# temp-sensor.net
KiCad netlist of a schematic drawn in EAGLE
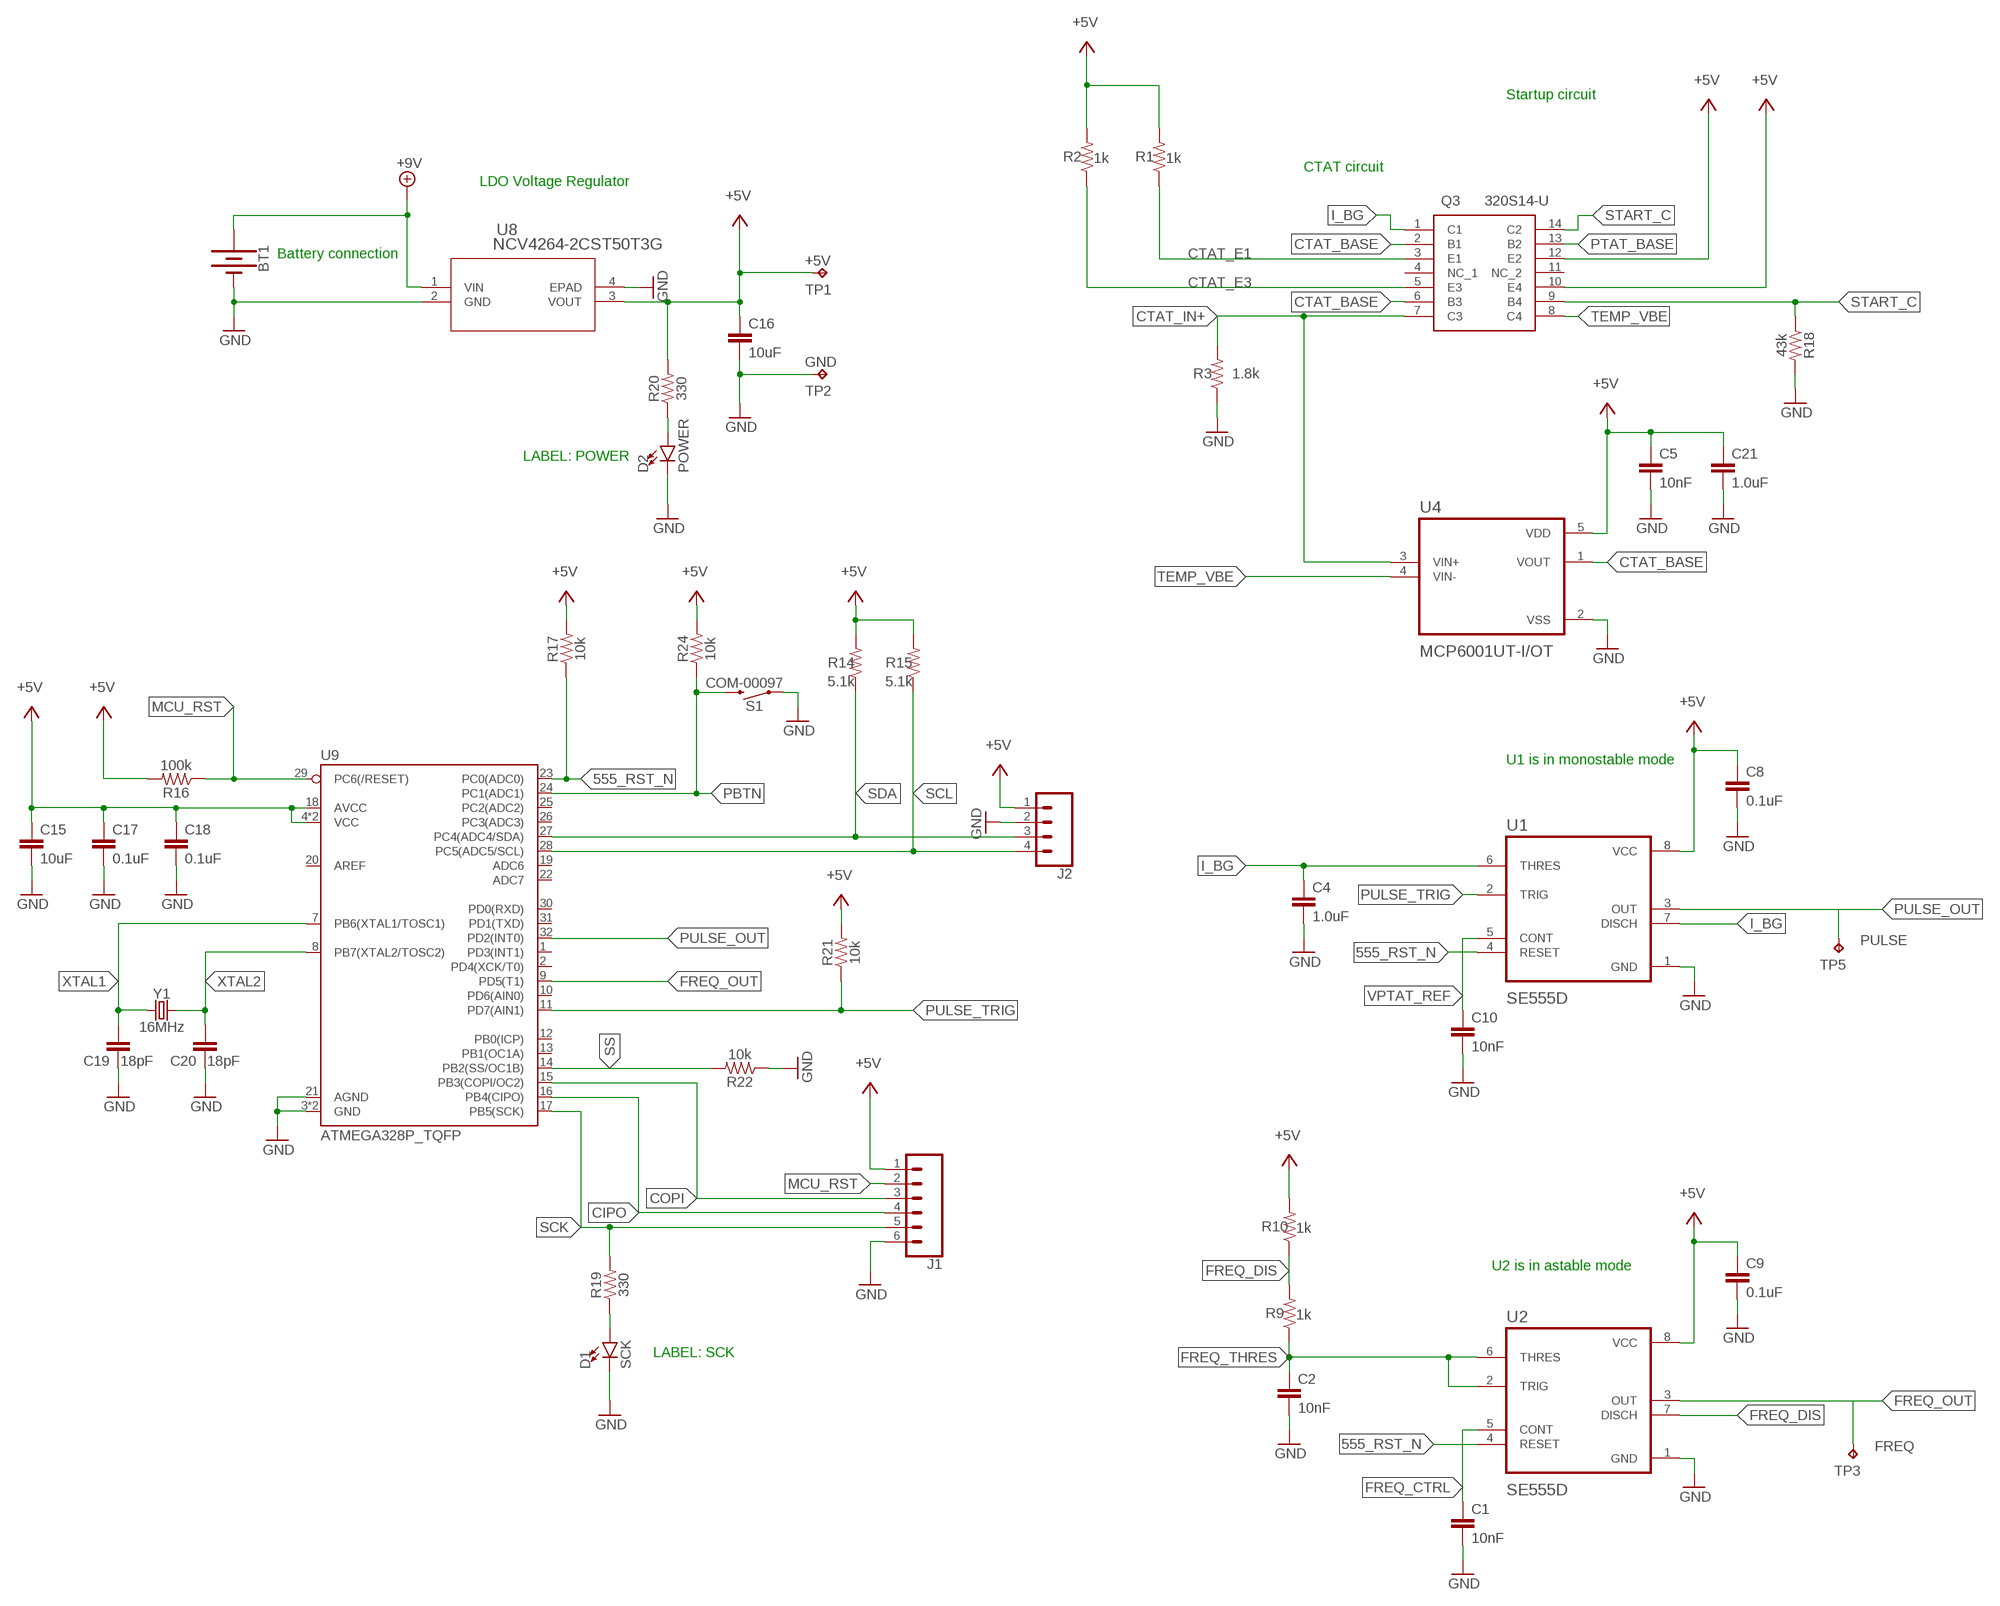
[diagram p0: schematic, sheet 1, part 1 of 2]
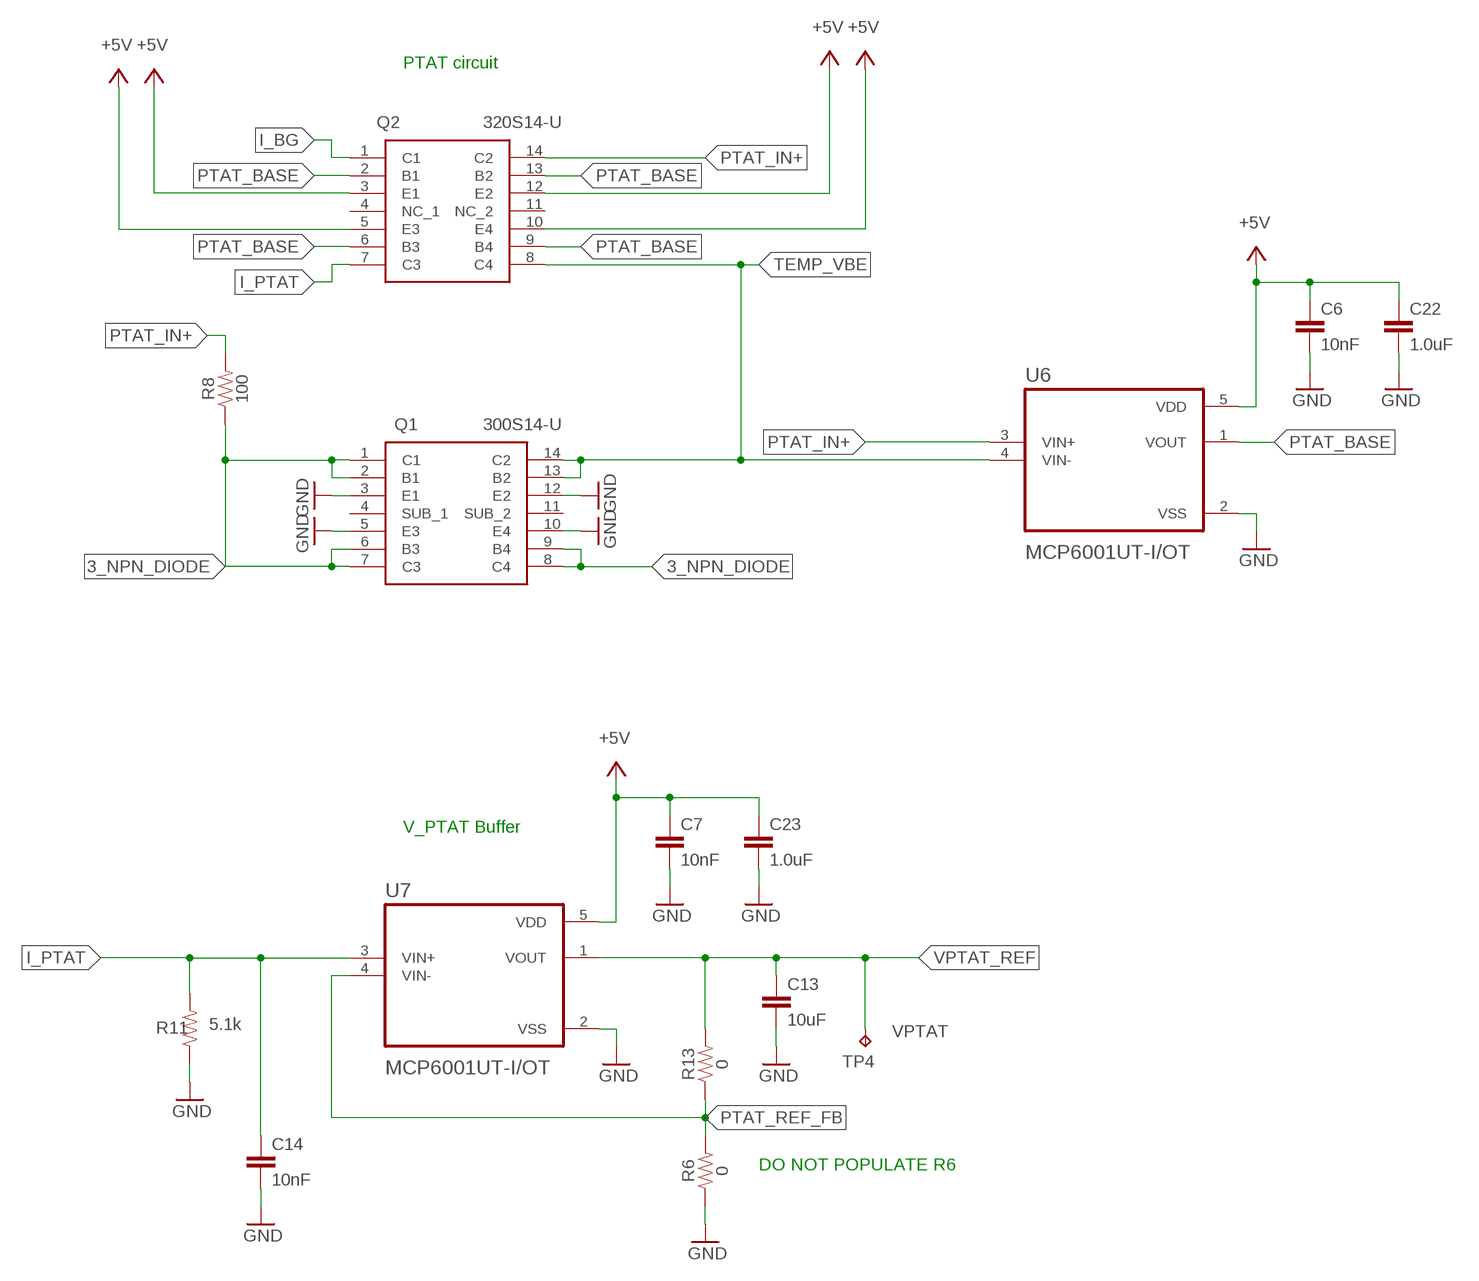
[diagram p1: schematic, sheet 1, part 2 of 2]

(export (version "E")
  (design (tool "Eeschema 10.0.6"))
  (components
    (comp (ref "BT1")
      (value "BATTERY-9V")
      (footprint "eagle-import:BATTCON_9V")
      (libsource (lib "eagle-import") (part "BATTERY-9V"))
    )
    (comp (ref "C1")
      (value "10nF")
      (footprint "eagle-import:0603")
      (libsource (lib "eagle-import") (part "10NF-0603-50V-10%"))
    )
    (comp (ref "C2")
      (value "10nF")
      (footprint "eagle-import:0603")
      (libsource (lib "eagle-import") (part "10NF-0603-50V-10%"))
    )
    (comp (ref "C4")
      (value "1.0uF")
      (footprint "eagle-import:0603")
      (libsource (lib "eagle-import") (part "1.0UF-0603-16V-10%-X7R"))
    )
    (comp (ref "C5")
      (value "10nF")
      (footprint "eagle-import:0603")
      (libsource (lib "eagle-import") (part "10NF-0603-50V-10%"))
    )
    (comp (ref "C6")
      (value "10nF")
      (footprint "eagle-import:0603")
      (libsource (lib "eagle-import") (part "10NF-0603-50V-10%"))
    )
    (comp (ref "C7")
      (value "10nF")
      (footprint "eagle-import:0603")
      (libsource (lib "eagle-import") (part "10NF-0603-50V-10%"))
    )
    (comp (ref "C8")
      (value "0.1uF")
      (footprint "eagle-import:0603")
      (libsource (lib "eagle-import") (part "0.1UF-0603-25V-10%-X7R-WE"))
    )
    (comp (ref "C9")
      (value "0.1uF")
      (footprint "eagle-import:0603")
      (libsource (lib "eagle-import") (part "0.1UF-0603-25V-10%-X7R-WE"))
    )
    (comp (ref "C10")
      (value "10nF")
      (footprint "eagle-import:0603")
      (libsource (lib "eagle-import") (part "10NF-0603-50V-10%"))
    )
    (comp (ref "C13")
      (value "10uF")
      (footprint "eagle-import:0805")
      (libsource (lib "eagle-import") (part "10UF-0805-25V-10%"))
    )
    (comp (ref "C14")
      (value "10nF")
      (footprint "eagle-import:0603")
      (libsource (lib "eagle-import") (part "10NF-0603-50V-10%"))
    )
    (comp (ref "C15")
      (value "10uF")
      (footprint "eagle-import:0805")
      (libsource (lib "eagle-import") (part "10UF-0805-25V-10%"))
    )
    (comp (ref "C16")
      (value "10uF")
      (footprint "eagle-import:0805")
      (libsource (lib "eagle-import") (part "10UF-0805-25V-10%"))
    )
    (comp (ref "C17")
      (value "0.1uF")
      (footprint "eagle-import:0603")
      (libsource (lib "eagle-import") (part "0.1UF-0603-25V-10%-X7R-WE"))
    )
    (comp (ref "C18")
      (value "0.1uF")
      (footprint "eagle-import:0603")
      (libsource (lib "eagle-import") (part "0.1UF-0603-25V-10%-X7R-WE"))
    )
    (comp (ref "C19")
      (value "18pF")
      (footprint "eagle-import:0603")
      (libsource (lib "eagle-import") (part "18PF-0603-50V-5%"))
    )
    (comp (ref "C20")
      (value "18pF")
      (footprint "eagle-import:0603")
      (libsource (lib "eagle-import") (part "18PF-0603-50V-5%"))
    )
    (comp (ref "C21")
      (value "1.0uF")
      (footprint "eagle-import:0603")
      (libsource (lib "eagle-import") (part "1.0UF-0603-16V-10%-X7R"))
    )
    (comp (ref "C22")
      (value "1.0uF")
      (footprint "eagle-import:0603")
      (libsource (lib "eagle-import") (part "1.0UF-0603-16V-10%-X7R"))
    )
    (comp (ref "C23")
      (value "1.0uF")
      (footprint "eagle-import:0603")
      (libsource (lib "eagle-import") (part "1.0UF-0603-16V-10%-X7R"))
    )
    (comp (ref "D1")
      (value "SCK")
      (footprint "eagle-import:LED-1206")
      (libsource (lib "eagle-import") (part "LED-GREEN1206"))
    )
    (comp (ref "D2")
      (value "POWER")
      (footprint "eagle-import:LED-1206")
      (libsource (lib "eagle-import") (part "LED-GREEN1206"))
    )
    (comp (ref "J1")
      (value "CONN_06SILK_FEMALE_PTH")
      (footprint "eagle-import:1X06")
      (libsource (lib "eagle-import") (part "CONN_06SILK_FEMALE_PTH"))
    )
    (comp (ref "J2")
      (value "CONN_04PTH")
      (footprint "eagle-import:1X04")
      (libsource (lib "eagle-import") (part "CONN_04PTH"))
    )
    (comp (ref "Q1")
      (value "300S14-U")
      (footprint "eagle-import:SOIC127P602X175-14N")
      (fields (field (name "MOUSER_PART_NUMBER") "887-300S14-U"))
      (libsource (lib "eagle-import") (part "300S14-U"))
    )
    (comp (ref "Q2")
      (value "320S14-U")
      (footprint "eagle-import:SOIC127P602X175-14N")
      (fields (field (name "MOUSER_PART_NUMBER") "887-320S14-U"))
      (libsource (lib "eagle-import") (part "320S14-U"))
    )
    (comp (ref "Q3")
      (value "320S14-U")
      (footprint "eagle-import:SOIC127P602X175-14N")
      (fields (field (name "MOUSER_PART_NUMBER") "887-320S14-U"))
      (libsource (lib "eagle-import") (part "320S14-U"))
    )
    (comp (ref "R1")
      (value "1k")
      (footprint "eagle-import:0603")
      (libsource (lib "eagle-import") (part "1KOHM-0603-1/10W-1%"))
    )
    (comp (ref "R2")
      (value "1k")
      (footprint "eagle-import:0603")
      (libsource (lib "eagle-import") (part "1KOHM-0603-1/10W-1%"))
    )
    (comp (ref "R3")
      (value "1.8k")
      (footprint "eagle-import:0603")
      (libsource (lib "eagle-import") (part "1.8KOHM-0603-1/10W-1%"))
    )
    (comp (ref "R6")
      (value "0")
      (footprint "eagle-import:0603")
      (libsource (lib "eagle-import") (part "0OHM-0603-1/10W"))
    )
    (comp (ref "R8")
      (value "100")
      (footprint "eagle-import:0603")
      (libsource (lib "eagle-import") (part "100OHM-0603-1/10W-1%"))
    )
    (comp (ref "R9")
      (value "1k")
      (footprint "eagle-import:0603")
      (libsource (lib "eagle-import") (part "1KOHM-0603-1/10W-1%"))
    )
    (comp (ref "R10")
      (value "1k")
      (footprint "eagle-import:0603")
      (libsource (lib "eagle-import") (part "1KOHM-0603-1/10W-1%"))
    )
    (comp (ref "R11")
      (value "5.1k")
      (footprint "eagle-import:0603")
      (libsource (lib "eagle-import") (part "5.1KOHM5.1KOHM-0603-1/10W-1%"))
    )
    (comp (ref "R13")
      (value "0")
      (footprint "eagle-import:0603")
      (libsource (lib "eagle-import") (part "0OHM-0603-1/10W"))
    )
    (comp (ref "R14")
      (value "5.1k")
      (footprint "eagle-import:0603")
      (libsource (lib "eagle-import") (part "5.1KOHM5.1KOHM-0603-1/10W-1%"))
    )
    (comp (ref "R15")
      (value "5.1k")
      (footprint "eagle-import:0603")
      (libsource (lib "eagle-import") (part "5.1KOHM5.1KOHM-0603-1/10W-1%"))
    )
    (comp (ref "R16")
      (value "100k")
      (footprint "eagle-import:0603")
      (libsource (lib "eagle-import") (part "100KOHM-0603-1/10W-1%"))
    )
    (comp (ref "R17")
      (value "10k")
      (footprint "eagle-import:0603")
      (libsource (lib "eagle-import") (part "10KOHM-0603-1/10W-1%"))
    )
    (comp (ref "R18")
      (value "43k")
      (footprint "eagle-import:0603")
      (libsource (lib "eagle-import") (part "43KOHM-0603-1/10W-1%"))
    )
    (comp (ref "R19")
      (value "330")
      (footprint "eagle-import:0603")
      (libsource (lib "eagle-import") (part "330OHM-0603-1/10W-1%"))
    )
    (comp (ref "R20")
      (value "330")
      (footprint "eagle-import:0603")
      (libsource (lib "eagle-import") (part "330OHM-0603-1/10W-1%"))
    )
    (comp (ref "R21")
      (value "10k")
      (footprint "eagle-import:0603")
      (libsource (lib "eagle-import") (part "10KOHM-0603-1/10W-1%"))
    )
    (comp (ref "R22")
      (value "10k")
      (footprint "eagle-import:0603")
      (libsource (lib "eagle-import") (part "10KOHM-0603-1/10W-1%"))
    )
    (comp (ref "R24")
      (value "10k")
      (footprint "eagle-import:0603")
      (libsource (lib "eagle-import") (part "10KOHM-0603-1/10W-1%"))
    )
    (comp (ref "S1")
      (value "MOMENTARY-SWITCH-SPST-PTH-6.0MM")
      (footprint "eagle-import:TACTILE_SWITCH_PTH_6.0MM")
      (fields (field (name "SF_SKU") "COM-00097"))
      (libsource (lib "eagle-import") (part "MOMENTARY-SWITCH-SPST-PTH-6.0MM"))
    )
    (comp (ref "TP1")
      (value "TPPAD1-13")
      (footprint "eagle-import:P1-13")
      (fields (field (name "TP_SIGNAL_NAME") "+5V"))
      (libsource (lib "eagle-import") (part "TPPAD1-13"))
    )
    (comp (ref "TP2")
      (value "TPPAD1-13")
      (footprint "eagle-import:P1-13")
      (fields (field (name "TP_SIGNAL_NAME") "GND"))
      (libsource (lib "eagle-import") (part "TPPAD1-13"))
    )
    (comp (ref "TP3")
      (value "TPPAD1-13")
      (footprint "eagle-import:P1-13")
      (fields (field (name "TP_SIGNAL_NAME") "FREQ"))
      (libsource (lib "eagle-import") (part "TPPAD1-13"))
    )
    (comp (ref "TP4")
      (value "TPPAD1-13")
      (footprint "eagle-import:P1-13")
      (fields (field (name "TP_SIGNAL_NAME") "VPTAT"))
      (libsource (lib "eagle-import") (part "TPPAD1-13"))
    )
    (comp (ref "TP5")
      (value "TPPAD1-13")
      (footprint "eagle-import:P1-13")
      (fields (field (name "TP_SIGNAL_NAME") "PULSE"))
      (libsource (lib "eagle-import") (part "TPPAD1-13"))
    )
    (comp (ref "U1")
      (value "SE555D")
      (footprint "eagle-import:SOIC127P599X175-8N")
      (fields (field (name "MF") "Texas Instruments"))
      (libsource (lib "eagle-import") (part "SE555D"))
    )
    (comp (ref "U2")
      (value "SE555D")
      (footprint "eagle-import:SOIC127P599X175-8N")
      (fields (field (name "MF") "Texas Instruments"))
      (libsource (lib "eagle-import") (part "SE555D"))
    )
    (comp (ref "U4")
      (value "MCP6001UT-I/OT")
      (footprint "eagle-import:SOT95P270X145-5N")
      (libsource (lib "eagle-import") (part "MCP6001UT-I/OT"))
    )
    (comp (ref "U6")
      (value "MCP6001UT-I/OT")
      (footprint "eagle-import:SOT95P270X145-5N")
      (libsource (lib "eagle-import") (part "MCP6001UT-I/OT"))
    )
    (comp (ref "U7")
      (value "MCP6001UT-I/OT")
      (footprint "eagle-import:SOT95P270X145-5N")
      (libsource (lib "eagle-import") (part "MCP6001UT-I/OT"))
    )
    (comp (ref "U8")
      (value "NCV4264-2CST50T3G")
      (footprint "eagle-import:SOT-223_ONS")
      (fields (field (name "COPYRIGHT") "Copyright (C) 2024 Ultra Librarian. All rights reserved."))
      (libsource (lib "eagle-import") (part "NCV4264-2CST50T3G"))
    )
    (comp (ref "U9")
      (value "ATMEGA328P_TQFP")
      (footprint "eagle-import:TQFP32-08")
      (libsource (lib "eagle-import") (part "ATMEGA328P_TQFP"))
    )
    (comp (ref "Y1")
      (value "16MHz")
      (footprint "eagle-import:CRYSTAL-SMD-5X3.2-4PAD")
      (libsource (lib "eagle-import") (part "CRYSTAL-16MHZSMD-5X3.2"))
    )
  )
  (nets
    (net (code "1") (name "+5V") (class "Default")
      (node (ref "C15") (pin "1") (pinfunction "1_1") (pintype "passive"))
      (node (ref "C16") (pin "1") (pinfunction "1_1") (pintype "passive"))
      (node (ref "C17") (pin "1") (pinfunction "1_1") (pintype "passive"))
      (node (ref "C18") (pin "1") (pinfunction "1_1") (pintype "passive"))
      (node (ref "C21") (pin "1") (pinfunction "1_1") (pintype "passive"))
      (node (ref "C22") (pin "1") (pinfunction "1_1") (pintype "passive"))
      (node (ref "C23") (pin "1") (pinfunction "1_1") (pintype "passive"))
      (node (ref "C5") (pin "1") (pinfunction "1_1") (pintype "passive"))
      (node (ref "C6") (pin "1") (pinfunction "1_1") (pintype "passive"))
      (node (ref "C7") (pin "1") (pinfunction "1_1") (pintype "passive"))
      (node (ref "C8") (pin "1") (pinfunction "1_1") (pintype "passive"))
      (node (ref "C9") (pin "1") (pinfunction "1_1") (pintype "passive"))
      (node (ref "J1") (pin "1") (pinfunction "1_1") (pintype "passive"))
      (node (ref "J2") (pin "1") (pinfunction "1_1") (pintype "passive"))
      (node (ref "Q2") (pin "10") (pinfunction "E4_10") (pintype "bidirectional"))
      (node (ref "Q2") (pin "12") (pinfunction "E2_12") (pintype "bidirectional"))
      (node (ref "Q2") (pin "3") (pinfunction "E1_3") (pintype "bidirectional"))
      (node (ref "Q2") (pin "5") (pinfunction "E3_5") (pintype "bidirectional"))
      (node (ref "Q3") (pin "10") (pinfunction "E4_10") (pintype "bidirectional"))
      (node (ref "Q3") (pin "12") (pinfunction "E2_12") (pintype "bidirectional"))
      (node (ref "R1") (pin "2") (pinfunction "2_2") (pintype "passive"))
      (node (ref "R10") (pin "2") (pinfunction "2_2") (pintype "passive"))
      (node (ref "R14") (pin "2") (pinfunction "2_2") (pintype "passive"))
      (node (ref "R15") (pin "2") (pinfunction "2_2") (pintype "passive"))
      (node (ref "R16") (pin "2") (pinfunction "2_2") (pintype "passive"))
      (node (ref "R17") (pin "2") (pinfunction "2_2") (pintype "passive"))
      (node (ref "R2") (pin "2") (pinfunction "2_2") (pintype "passive"))
      (node (ref "R20") (pin "2") (pinfunction "2_2") (pintype "passive"))
      (node (ref "R21") (pin "2") (pinfunction "2_2") (pintype "passive"))
      (node (ref "R24") (pin "2") (pinfunction "2_2") (pintype "passive"))
      (node (ref "TP1") (pin "TP") (pinfunction "TP_TP") (pintype "input"))
      (node (ref "U1") (pin "8") (pinfunction "VCC_8") (pintype "power_in"))
      (node (ref "U2") (pin "8") (pinfunction "VCC_8") (pintype "power_in"))
      (node (ref "U4") (pin "5") (pinfunction "VDD_5") (pintype "power_in"))
      (node (ref "U6") (pin "5") (pinfunction "VDD_5") (pintype "power_in"))
      (node (ref "U7") (pin "5") (pinfunction "VDD_5") (pintype "power_in"))
      (node (ref "U8") (pin "3") (pinfunction "VOUT_3") (pintype "output"))
      (node (ref "U9") (pin "18") (pinfunction "AVCC_18") (pintype "bidirectional"))
      (node (ref "U9") (pin "4") (pinfunction "VCC_4") (pintype "bidirectional"))
      (node (ref "U9") (pin "6") (pinfunction "VCC_6") (pintype "bidirectional"))
    )
    (net (code "2") (name "+9V") (class "Default")
      (node (ref "BT1") (pin "+") (pinfunction "+_+") (pintype "power_in"))
      (node (ref "U8") (pin "1") (pinfunction "VIN_1") (pintype "passive"))
    )
    (net (code "3") (name "/CTAT_E1") (class "Default")
      (node (ref "Q3") (pin "3") (pinfunction "E1_3") (pintype "bidirectional"))
      (node (ref "R1") (pin "1") (pinfunction "1_1") (pintype "passive"))
    )
    (net (code "4") (name "/CTAT_E3") (class "Default")
      (node (ref "Q3") (pin "5") (pinfunction "E3_5") (pintype "bidirectional"))
      (node (ref "R2") (pin "1") (pinfunction "1_1") (pintype "passive"))
    )
    (net (code "5") (name "3_NPN_DIODE") (class "Default")
      (node (ref "Q1") (pin "1") (pinfunction "C1_1") (pintype "bidirectional"))
      (node (ref "Q1") (pin "2") (pinfunction "B1_2") (pintype "bidirectional"))
      (node (ref "Q1") (pin "6") (pinfunction "B3_6") (pintype "bidirectional"))
      (node (ref "Q1") (pin "7") (pinfunction "C3_7") (pintype "bidirectional"))
      (node (ref "Q1") (pin "8") (pinfunction "C4_8") (pintype "bidirectional"))
      (node (ref "Q1") (pin "9") (pinfunction "B4_9") (pintype "bidirectional"))
      (node (ref "R8") (pin "1") (pinfunction "1_1") (pintype "passive"))
    )
    (net (code "6") (name "555_RST_N") (class "Default")
      (node (ref "R17") (pin "1") (pinfunction "1_1") (pintype "passive"))
      (node (ref "U1") (pin "4") (pinfunction "RESET_4") (pintype "input"))
      (node (ref "U2") (pin "4") (pinfunction "RESET_4") (pintype "input"))
      (node (ref "U9") (pin "23") (pinfunction "PC0(ADC0)_23") (pintype "bidirectional"))
    )
    (net (code "7") (name "CIPO") (class "Default")
      (node (ref "J1") (pin "4") (pinfunction "4_4") (pintype "passive"))
      (node (ref "U9") (pin "16") (pinfunction "PB4(CIPO)_16") (pintype "bidirectional"))
    )
    (net (code "8") (name "COPI") (class "Default")
      (node (ref "J1") (pin "3") (pinfunction "3_3") (pintype "passive"))
      (node (ref "U9") (pin "15") (pinfunction "PB3(COPI/OC2)_15") (pintype "bidirectional"))
    )
    (net (code "9") (name "CTAT_BASE") (class "Default")
      (node (ref "Q3") (pin "2") (pinfunction "B1_2") (pintype "bidirectional"))
      (node (ref "Q3") (pin "6") (pinfunction "B3_6") (pintype "bidirectional"))
      (node (ref "U4") (pin "1") (pinfunction "VOUT_1") (pintype "output"))
    )
    (net (code "10") (name "CTAT_IN+") (class "Default")
      (node (ref "Q3") (pin "7") (pinfunction "C3_7") (pintype "bidirectional"))
      (node (ref "R3") (pin "2") (pinfunction "2_2") (pintype "passive"))
      (node (ref "U4") (pin "3") (pinfunction "VIN+_3") (pintype "input"))
    )
    (net (code "11") (name "FREQ_CTRL") (class "Default")
      (node (ref "C1") (pin "1") (pinfunction "1_1") (pintype "passive"))
      (node (ref "U2") (pin "5") (pinfunction "CONT_5") (pintype "bidirectional"))
    )
    (net (code "12") (name "FREQ_DIS") (class "Default")
      (node (ref "R10") (pin "1") (pinfunction "1_1") (pintype "passive"))
      (node (ref "R9") (pin "2") (pinfunction "2_2") (pintype "passive"))
      (node (ref "U2") (pin "7") (pinfunction "DISCH_7") (pintype "output"))
    )
    (net (code "13") (name "FREQ_OUT") (class "Default")
      (node (ref "TP3") (pin "TP") (pinfunction "TP_TP") (pintype "input"))
      (node (ref "U2") (pin "3") (pinfunction "OUT_3") (pintype "output"))
      (node (ref "U9") (pin "9") (pinfunction "PD5(T1)_9") (pintype "bidirectional"))
    )
    (net (code "14") (name "FREQ_THRES") (class "Default")
      (node (ref "C2") (pin "1") (pinfunction "1_1") (pintype "passive"))
      (node (ref "R9") (pin "1") (pinfunction "1_1") (pintype "passive"))
      (node (ref "U2") (pin "2") (pinfunction "TRIG_2") (pintype "input"))
      (node (ref "U2") (pin "6") (pinfunction "THRES_6") (pintype "input"))
    )
    (net (code "15") (name "GND") (class "Default")
      (node (ref "BT1") (pin "-") (pinfunction "-_-") (pintype "power_in"))
      (node (ref "C1") (pin "2") (pinfunction "2_2") (pintype "passive"))
      (node (ref "C10") (pin "2") (pinfunction "2_2") (pintype "passive"))
      (node (ref "C13") (pin "2") (pinfunction "2_2") (pintype "passive"))
      (node (ref "C14") (pin "2") (pinfunction "2_2") (pintype "passive"))
      (node (ref "C15") (pin "2") (pinfunction "2_2") (pintype "passive"))
      (node (ref "C16") (pin "2") (pinfunction "2_2") (pintype "passive"))
      (node (ref "C17") (pin "2") (pinfunction "2_2") (pintype "passive"))
      (node (ref "C18") (pin "2") (pinfunction "2_2") (pintype "passive"))
      (node (ref "C19") (pin "1") (pinfunction "1_1") (pintype "passive"))
      (node (ref "C2") (pin "2") (pinfunction "2_2") (pintype "passive"))
      (node (ref "C20") (pin "1") (pinfunction "1_1") (pintype "passive"))
      (node (ref "C21") (pin "2") (pinfunction "2_2") (pintype "passive"))
      (node (ref "C22") (pin "2") (pinfunction "2_2") (pintype "passive"))
      (node (ref "C23") (pin "2") (pinfunction "2_2") (pintype "passive"))
      (node (ref "C4") (pin "2") (pinfunction "2_2") (pintype "passive"))
      (node (ref "C5") (pin "2") (pinfunction "2_2") (pintype "passive"))
      (node (ref "C6") (pin "2") (pinfunction "2_2") (pintype "passive"))
      (node (ref "C7") (pin "2") (pinfunction "2_2") (pintype "passive"))
      (node (ref "C8") (pin "2") (pinfunction "2_2") (pintype "passive"))
      (node (ref "C9") (pin "2") (pinfunction "2_2") (pintype "passive"))
      (node (ref "D1") (pin "C") (pinfunction "C_C") (pintype "passive"))
      (node (ref "D2") (pin "C") (pinfunction "C_C") (pintype "passive"))
      (node (ref "J1") (pin "6") (pinfunction "6_6") (pintype "passive"))
      (node (ref "J2") (pin "2") (pinfunction "2_2") (pintype "passive"))
      (node (ref "Q1") (pin "10") (pinfunction "E4_10") (pintype "bidirectional"))
      (node (ref "Q1") (pin "12") (pinfunction "E2_12") (pintype "bidirectional"))
      (node (ref "Q1") (pin "3") (pinfunction "E1_3") (pintype "bidirectional"))
      (node (ref "Q1") (pin "5") (pinfunction "E3_5") (pintype "bidirectional"))
      (node (ref "R11") (pin "1") (pinfunction "1_1") (pintype "passive"))
      (node (ref "R18") (pin "2") (pinfunction "2_2") (pintype "passive"))
      (node (ref "R22") (pin "1") (pinfunction "1_1") (pintype "passive"))
      (node (ref "R3") (pin "1") (pinfunction "1_1") (pintype "passive"))
      (node (ref "R6") (pin "1") (pinfunction "1_1") (pintype "passive"))
      (node (ref "S1") (pin "1") (pinfunction "1_1") (pintype "passive"))
      (node (ref "TP2") (pin "TP") (pinfunction "TP_TP") (pintype "input"))
      (node (ref "U1") (pin "1") (pinfunction "GND_1") (pintype "power_in"))
      (node (ref "U2") (pin "1") (pinfunction "GND_1") (pintype "power_in"))
      (node (ref "U4") (pin "2") (pinfunction "VSS_2") (pintype "power_in"))
      (node (ref "U6") (pin "2") (pinfunction "VSS_2") (pintype "power_in"))
      (node (ref "U7") (pin "2") (pinfunction "VSS_2") (pintype "power_in"))
      (node (ref "U8") (pin "2") (pinfunction "GND_2") (pintype "passive"))
      (node (ref "U8") (pin "4") (pinfunction "EPAD_4") (pintype "passive"))
      (node (ref "U9") (pin "21") (pinfunction "AGND_21") (pintype "bidirectional"))
      (node (ref "U9") (pin "3") (pinfunction "GND_3") (pintype "bidirectional"))
      (node (ref "U9") (pin "5") (pinfunction "GND_5") (pintype "bidirectional"))
    )
    (net (code "16") (name "I_BG") (class "Default")
      (node (ref "C4") (pin "1") (pinfunction "1_1") (pintype "passive"))
      (node (ref "Q2") (pin "1") (pinfunction "C1_1") (pintype "bidirectional"))
      (node (ref "Q3") (pin "1") (pinfunction "C1_1") (pintype "bidirectional"))
      (node (ref "U1") (pin "6") (pinfunction "THRES_6") (pintype "input"))
      (node (ref "U1") (pin "7") (pinfunction "DISCH_7") (pintype "output"))
    )
    (net (code "17") (name "I_PTAT") (class "Default")
      (node (ref "C14") (pin "1") (pinfunction "1_1") (pintype "passive"))
      (node (ref "Q2") (pin "7") (pinfunction "C3_7") (pintype "bidirectional"))
      (node (ref "R11") (pin "2") (pinfunction "2_2") (pintype "passive"))
      (node (ref "U7") (pin "3") (pinfunction "VIN+_3") (pintype "input"))
    )
    (net (code "18") (name "MCU_RST") (class "Default")
      (node (ref "J1") (pin "2") (pinfunction "2_2") (pintype "passive"))
      (node (ref "R16") (pin "1") (pinfunction "1_1") (pintype "passive"))
      (node (ref "U9") (pin "29") (pinfunction "PC6(/RESET)_29") (pintype "bidirectional"))
    )
    (net (code "19") (name "Net-(D1-PadA)") (class "Default")
      (node (ref "D1") (pin "A") (pinfunction "A_A") (pintype "passive"))
      (node (ref "R19") (pin "1") (pinfunction "1_1") (pintype "passive"))
    )
    (net (code "20") (name "Net-(D2-PadA)") (class "Default")
      (node (ref "D2") (pin "A") (pinfunction "A_A") (pintype "passive"))
      (node (ref "R20") (pin "1") (pinfunction "1_1") (pintype "passive"))
    )
    (net (code "21") (name "PBTN") (class "Default")
      (node (ref "R24") (pin "1") (pinfunction "1_1") (pintype "passive"))
      (node (ref "S1") (pin "3") (pinfunction "2_3") (pintype "passive"))
      (node (ref "U9") (pin "24") (pinfunction "PC1(ADC1)_24") (pintype "bidirectional"))
    )
    (net (code "22") (name "PTAT_BASE") (class "Default")
      (node (ref "Q2") (pin "13") (pinfunction "B2_13") (pintype "bidirectional"))
      (node (ref "Q2") (pin "2") (pinfunction "B1_2") (pintype "bidirectional"))
      (node (ref "Q2") (pin "6") (pinfunction "B3_6") (pintype "bidirectional"))
      (node (ref "Q2") (pin "9") (pinfunction "B4_9") (pintype "bidirectional"))
      (node (ref "Q3") (pin "13") (pinfunction "B2_13") (pintype "bidirectional"))
      (node (ref "U6") (pin "1") (pinfunction "VOUT_1") (pintype "output"))
    )
    (net (code "23") (name "PTAT_IN+") (class "Default")
      (node (ref "Q2") (pin "14") (pinfunction "C2_14") (pintype "bidirectional"))
      (node (ref "R8") (pin "2") (pinfunction "2_2") (pintype "passive"))
      (node (ref "U6") (pin "3") (pinfunction "VIN+_3") (pintype "input"))
    )
    (net (code "24") (name "PTAT_REF_FB") (class "Default")
      (node (ref "R13") (pin "1") (pinfunction "1_1") (pintype "passive"))
      (node (ref "R6") (pin "2") (pinfunction "2_2") (pintype "passive"))
      (node (ref "U7") (pin "4") (pinfunction "VIN-_4") (pintype "input"))
    )
    (net (code "25") (name "PULSE_OUT") (class "Default")
      (node (ref "TP5") (pin "TP") (pinfunction "TP_TP") (pintype "input"))
      (node (ref "U1") (pin "3") (pinfunction "OUT_3") (pintype "output"))
      (node (ref "U9") (pin "32") (pinfunction "PD2(INT0)_32") (pintype "bidirectional"))
    )
    (net (code "26") (name "PULSE_TRIG") (class "Default")
      (node (ref "R21") (pin "1") (pinfunction "1_1") (pintype "passive"))
      (node (ref "U1") (pin "2") (pinfunction "TRIG_2") (pintype "input"))
      (node (ref "U9") (pin "11") (pinfunction "PD7(AIN1)_11") (pintype "bidirectional"))
    )
    (net (code "27") (name "SCK") (class "Default")
      (node (ref "J1") (pin "5") (pinfunction "5_5") (pintype "passive"))
      (node (ref "R19") (pin "2") (pinfunction "2_2") (pintype "passive"))
      (node (ref "U9") (pin "17") (pinfunction "PB5(SCK)_17") (pintype "bidirectional"))
    )
    (net (code "28") (name "SCL") (class "Default")
      (node (ref "J2") (pin "4") (pinfunction "4_4") (pintype "passive"))
      (node (ref "R15") (pin "1") (pinfunction "1_1") (pintype "passive"))
      (node (ref "U9") (pin "28") (pinfunction "PC5(ADC5/SCL)_28") (pintype "bidirectional"))
    )
    (net (code "29") (name "SDA") (class "Default")
      (node (ref "J2") (pin "3") (pinfunction "3_3") (pintype "passive"))
      (node (ref "R14") (pin "1") (pinfunction "1_1") (pintype "passive"))
      (node (ref "U9") (pin "27") (pinfunction "PC4(ADC4/SDA)_27") (pintype "bidirectional"))
    )
    (net (code "30") (name "SS") (class "Default")
      (node (ref "R22") (pin "2") (pinfunction "2_2") (pintype "passive"))
      (node (ref "U9") (pin "14") (pinfunction "PB2(SS/OC1B)_14") (pintype "bidirectional"))
    )
    (net (code "31") (name "START_C") (class "Default")
      (node (ref "Q3") (pin "14") (pinfunction "C2_14") (pintype "bidirectional"))
      (node (ref "Q3") (pin "9") (pinfunction "B4_9") (pintype "bidirectional"))
      (node (ref "R18") (pin "1") (pinfunction "1_1") (pintype "passive"))
    )
    (net (code "32") (name "TEMP_VBE") (class "Default")
      (node (ref "Q1") (pin "13") (pinfunction "B2_13") (pintype "bidirectional"))
      (node (ref "Q1") (pin "14") (pinfunction "C2_14") (pintype "bidirectional"))
      (node (ref "Q2") (pin "8") (pinfunction "C4_8") (pintype "bidirectional"))
      (node (ref "Q3") (pin "8") (pinfunction "C4_8") (pintype "bidirectional"))
      (node (ref "U4") (pin "4") (pinfunction "VIN-_4") (pintype "input"))
      (node (ref "U6") (pin "4") (pinfunction "VIN-_4") (pintype "input"))
    )
    (net (code "33") (name "VPTAT_REF") (class "Default")
      (node (ref "C10") (pin "1") (pinfunction "1_1") (pintype "passive"))
      (node (ref "C13") (pin "1") (pinfunction "1_1") (pintype "passive"))
      (node (ref "R13") (pin "2") (pinfunction "2_2") (pintype "passive"))
      (node (ref "TP4") (pin "TP") (pinfunction "TP_TP") (pintype "input"))
      (node (ref "U1") (pin "5") (pinfunction "CONT_5") (pintype "bidirectional"))
      (node (ref "U7") (pin "1") (pinfunction "VOUT_1") (pintype "output"))
    )
    (net (code "34") (name "XTAL1") (class "Default")
      (node (ref "C19") (pin "2") (pinfunction "2_2") (pintype "passive"))
      (node (ref "U9") (pin "7") (pinfunction "PB6(XTAL1/TOSC1)_7") (pintype "bidirectional"))
      (node (ref "Y1") (pin "1") (pinfunction "1_1") (pintype "passive"))
    )
    (net (code "35") (name "XTAL2") (class "Default")
      (node (ref "C20") (pin "2") (pinfunction "2_2") (pintype "passive"))
      (node (ref "U9") (pin "8") (pinfunction "PB7(XTAL2/TOSC2)_8") (pintype "bidirectional"))
      (node (ref "Y1") (pin "3") (pinfunction "2_3") (pintype "passive"))
    )
    (net (code "36") (name "unconnected-(Q1-SUB_1-Pad4)") (class "Default")
      (node (ref "Q1") (pin "4") (pinfunction "SUB_1_4") (pintype "bidirectional"))
    )
    (net (code "37") (name "unconnected-(Q1-SUB_2-Pad11)") (class "Default")
      (node (ref "Q1") (pin "11") (pinfunction "SUB_2_11") (pintype "bidirectional"))
    )
    (net (code "38") (name "unconnected-(Q2-NC_1-Pad4)") (class "Default")
      (node (ref "Q2") (pin "4") (pinfunction "NC_1_4") (pintype "bidirectional"))
    )
    (net (code "39") (name "unconnected-(Q2-NC_2-Pad11)") (class "Default")
      (node (ref "Q2") (pin "11") (pinfunction "NC_2_11") (pintype "bidirectional"))
    )
    (net (code "40") (name "unconnected-(Q3-NC_1-Pad4)") (class "Default")
      (node (ref "Q3") (pin "4") (pinfunction "NC_1_4") (pintype "bidirectional"))
    )
    (net (code "41") (name "unconnected-(Q3-NC_2-Pad11)") (class "Default")
      (node (ref "Q3") (pin "11") (pinfunction "NC_2_11") (pintype "bidirectional"))
    )
    (net (code "42") (name "unconnected-(U9-ADC6-Pad19)") (class "Default")
      (node (ref "U9") (pin "19") (pinfunction "ADC6_19") (pintype "bidirectional"))
    )
    (net (code "43") (name "unconnected-(U9-ADC7-Pad22)") (class "Default")
      (node (ref "U9") (pin "22") (pinfunction "ADC7_22") (pintype "bidirectional"))
    )
    (net (code "44") (name "unconnected-(U9-AREF-Pad20)") (class "Default")
      (node (ref "U9") (pin "20") (pinfunction "AREF_20") (pintype "bidirectional"))
    )
    (net (code "45") (name "unconnected-(U9-PB0(ICP)-Pad12)") (class "Default")
      (node (ref "U9") (pin "12") (pinfunction "PB0(ICP)_12") (pintype "bidirectional"))
    )
    (net (code "46") (name "unconnected-(U9-PB1(OC1A)-Pad13)") (class "Default")
      (node (ref "U9") (pin "13") (pinfunction "PB1(OC1A)_13") (pintype "bidirectional"))
    )
    (net (code "47") (name "unconnected-(U9-PC2(ADC2)-Pad25)") (class "Default")
      (node (ref "U9") (pin "25") (pinfunction "PC2(ADC2)_25") (pintype "bidirectional"))
    )
    (net (code "48") (name "unconnected-(U9-PC3(ADC3)-Pad26)") (class "Default")
      (node (ref "U9") (pin "26") (pinfunction "PC3(ADC3)_26") (pintype "bidirectional"))
    )
    (net (code "49") (name "unconnected-(U9-PD0(RXD)-Pad30)") (class "Default")
      (node (ref "U9") (pin "30") (pinfunction "PD0(RXD)_30") (pintype "bidirectional"))
    )
    (net (code "50") (name "unconnected-(U9-PD1(TXD)-Pad31)") (class "Default")
      (node (ref "U9") (pin "31") (pinfunction "PD1(TXD)_31") (pintype "bidirectional"))
    )
    (net (code "51") (name "unconnected-(U9-PD3(INT1)-Pad1)") (class "Default")
      (node (ref "U9") (pin "1") (pinfunction "PD3(INT1)_1") (pintype "bidirectional"))
    )
    (net (code "52") (name "unconnected-(U9-PD4(XCK{slash}T0)-Pad2)") (class "Default")
      (node (ref "U9") (pin "2") (pinfunction "PD4(XCK/T0)_2") (pintype "bidirectional"))
    )
    (net (code "53") (name "unconnected-(U9-PD6(AIN0)-Pad10)") (class "Default")
      (node (ref "U9") (pin "10") (pinfunction "PD6(AIN0)_10") (pintype "bidirectional"))
    )
  )
)
